# MR_UartConnector.net
KiCad netlist of a schematic drawn in Altium Designer
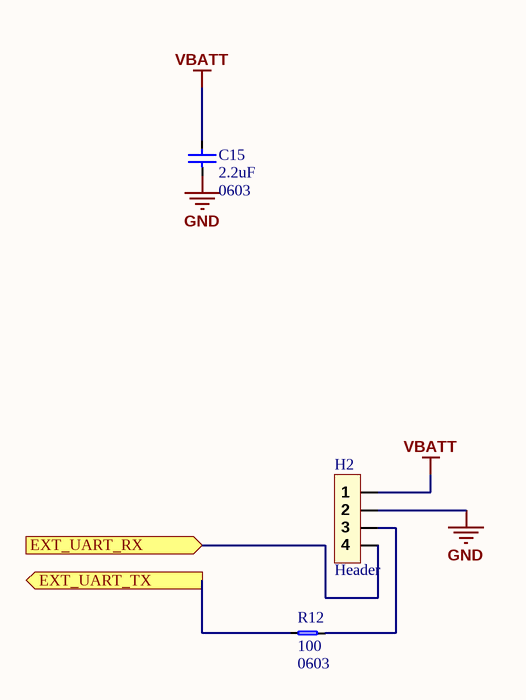
[diagram p0: MR_UartConnector.SchDoc]

(export (version "E")
  (design (tool "Eeschema 10.0.6"))
  (components
    (comp (ref "C15")
      (value "2.2uF")
      (footprint "0603_CAP_LD")
      (description "Ceramic Capacitor")
      (fields (field (name "PACKAGE") "0603") (field (name "Comment") "CerCap"))
      (libsource (lib "MiniRobot") (part "CerCap"))
    )
    (comp (ref "H2")
      (value "Header")
      (footprint "HE14 1x4 Straight")
      (description "Header 4x1 PIns")
      (libsource (lib "MiniRobot") (part "Header_4x1"))
    )
    (comp (ref "R12")
      (value "100")
      (footprint "0603_RES_LD")
      (description "Resistor")
      (fields (field (name "PACKAGE") "0603"))
      (libsource (lib "MiniRobot") (part "Resistor"))
    )
  )
  (nets
    (net (code "1") (name "/EXT_UART_RX") (class "Default")
      (node (ref "H2") (pin "4") (pinfunction "4_4") (pintype "passive"))
    )
    (net (code "2") (name "/EXT_UART_TX") (class "Default")
      (node (ref "R12") (pin "1") (pinfunction "1_1") (pintype "passive"))
    )
    (net (code "3") (name "GND") (class "Default")
      (node (ref "C15") (pin "1") (pinfunction "1_1") (pintype "passive"))
      (node (ref "H2") (pin "2") (pinfunction "2_2") (pintype "passive"))
    )
    (net (code "4") (name "Net-(H2-Pad3)") (class "Default")
      (node (ref "H2") (pin "3") (pinfunction "3_3") (pintype "passive"))
      (node (ref "R12") (pin "2") (pinfunction "2_2") (pintype "passive"))
    )
    (net (code "5") (name "VBATT") (class "Default")
      (node (ref "C15") (pin "2") (pinfunction "2_2") (pintype "passive"))
      (node (ref "H2") (pin "1") (pinfunction "1_1") (pintype "passive"))
    )
  )
)
